# MKE1xFxxxVLH.net
KiCad netlist of a schematic drawn in Altium Designer
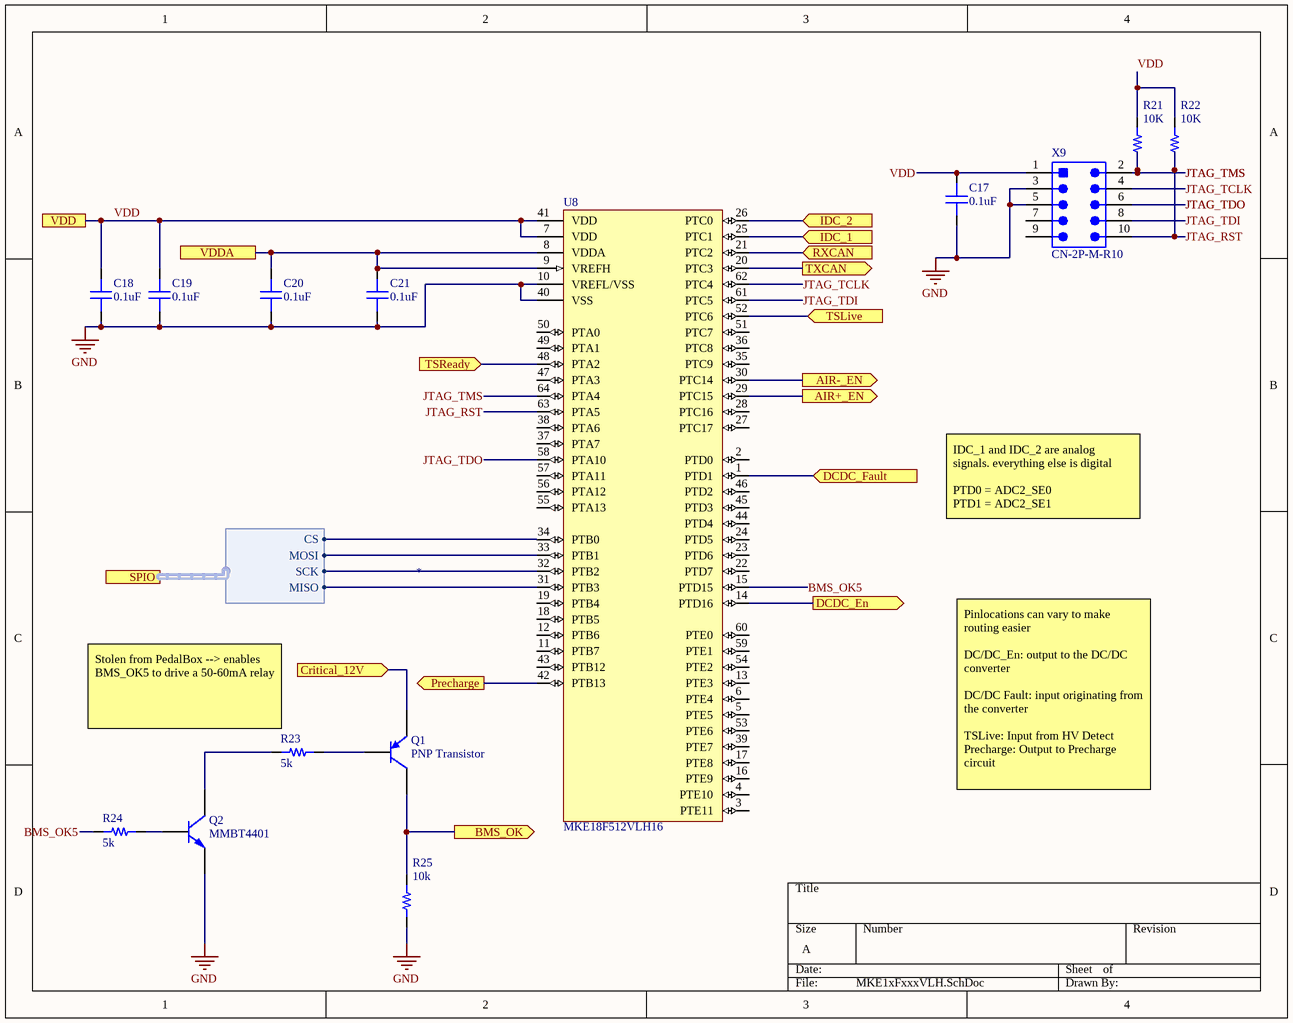
[diagram p0: MKE1xFxxxVLH.SchDoc]

(export (version "E")
  (design (tool "Eeschema 10.0.6"))
  (components
    (comp (ref "C17")
      (value "capacitor")
      (footprint "0603")
      (description "Generic 0603 capacitor")
      (fields (field (name "CAPACITANCE") "0.1uF") (field (name "VOLTAGE") "50"))
      (libsource (lib "altlib") (part "capacitor"))
    )
    (comp (ref "C18")
      (value "capacitor")
      (footprint "0603")
      (description "Generic 0603 capacitor")
      (fields (field (name "CAPACITANCE") "0.1uF") (field (name "VOLTAGE") "50"))
      (libsource (lib "altlib") (part "capacitor"))
    )
    (comp (ref "C19")
      (value "capacitor")
      (footprint "0603")
      (description "Generic 0603 capacitor")
      (fields (field (name "CAPACITANCE") "0.1uF") (field (name "VOLTAGE") "50"))
      (libsource (lib "altlib") (part "capacitor"))
    )
    (comp (ref "C20")
      (value "capacitor")
      (footprint "0603")
      (description "Generic 0603 capacitor")
      (fields (field (name "CAPACITANCE") "0.1uF") (field (name "VOLTAGE") "50"))
      (libsource (lib "altlib") (part "capacitor"))
    )
    (comp (ref "C21")
      (value "capacitor")
      (footprint "0603")
      (description "Generic 0603 capacitor")
      (fields (field (name "CAPACITANCE") "0.1uF") (field (name "VOLTAGE") "50"))
      (libsource (lib "altlib") (part "capacitor"))
    )
    (comp (ref "Q1")
      (value "PNP Transistor")
      (footprint "SOT23-3")
      (description "Bipolar (BJT) Transistor PNP 25V 1.5A 100MHz")
      (fields (field (name "POWER") "625") (field (name "CREATEDBY") "Kevin"))
      (libsource (lib "altlib") (part "PNP Transistor"))
    )
    (comp (ref "Q2") (value "MMBT4401") (footprint "SOT23-3") (libsource (lib "altlib") (part "MMBT4401")))
    (comp (ref "R21")
      (value "10K")
      (footprint "RES 0603/1608")
      (fields (field (name "RESISTANCE") "10K"))
      (libsource (lib "altlib") (part "Resistor"))
    )
    (comp (ref "R22")
      (value "10K")
      (footprint "RES 0603/1608")
      (fields (field (name "RESISTANCE") "10K"))
      (libsource (lib "altlib") (part "Resistor"))
    )
    (comp (ref "R23")
      (value "5k")
      (footprint "RES 0603/1608")
      (fields (field (name "RESISTANCE") "5k"))
      (libsource (lib "altlib") (part "Resistor"))
    )
    (comp (ref "R24")
      (value "5k")
      (footprint "RES 0603/1608")
      (fields (field (name "RESISTANCE") "5k"))
      (libsource (lib "altlib") (part "Resistor"))
    )
    (comp (ref "R25")
      (value "10k")
      (footprint "RES 0603/1608")
      (fields (field (name "RESISTANCE") "10k"))
      (libsource (lib "altlib") (part "Resistor"))
    )
    (comp (ref "U8")
      (value "MKE18F512VLH16")
      (footprint "TQFP64")
      (description "32b NXP Microcontroller")
      (libsource (lib "altlib") (part "MKE18F512VLH16"))
    )
    (comp (ref "X9")
      (value "CN-2P-M-R10")
      (footprint "HDR2X5_SMT")
      (description "CONN_TE_2X5POS")
      (libsource (lib "altlib") (part "CN-2P-M-R10"))
    )
  )
  (nets
    (net (code "2") (name "/AIR+_EN") (class "Default")
      (node (ref "U8") (pin "29") (pinfunction "PTC15_29") (pintype "bidirectional"))
    )
    (net (code "3") (name "/AIR-_EN") (class "Default")
      (node (ref "U8") (pin "30") (pinfunction "PTC14_30") (pintype "bidirectional"))
    )
    (net (code "4") (name "/BMS_OK") (class "Default")
      (node (ref "Q1") (pin "3") (pinfunction "C_3") (pintype "passive"))
      (node (ref "R25") (pin "2") (pinfunction "2_2") (pintype "passive"))
    )
    (net (code "5") (name "/BMS_OK5") (class "Default")
      (node (ref "R24") (pin "2") (pinfunction "2_2") (pintype "passive"))
      (node (ref "U8") (pin "15") (pinfunction "PTD15_15") (pintype "bidirectional"))
    )
    (net (code "6") (name "/CS") (class "Default")
      (node (ref "U8") (pin "34") (pinfunction "PTB0_34") (pintype "bidirectional"))
    )
    (net (code "7") (name "/Critical_12V") (class "Default")
      (node (ref "Q1") (pin "2") (pinfunction "E_2") (pintype "passive"))
    )
    (net (code "8") (name "/DCDC_En") (class "Default")
      (node (ref "U8") (pin "14") (pinfunction "PTD16_14") (pintype "bidirectional"))
    )
    (net (code "9") (name "/DCDC_Fault") (class "Default")
      (node (ref "U8") (pin "1") (pinfunction "PTD1_1") (pintype "bidirectional"))
    )
    (net (code "10") (name "/IDC_1") (class "Default")
      (node (ref "U8") (pin "25") (pinfunction "PTC1_25") (pintype "bidirectional"))
    )
    (net (code "11") (name "/IDC_2") (class "Default")
      (node (ref "U8") (pin "26") (pinfunction "PTC0_26") (pintype "bidirectional"))
    )
    (net (code "12") (name "/JTAG_RST") (class "Default")
      (node (ref "R22") (pin "1") (pinfunction "1_1") (pintype "passive"))
      (node (ref "U8") (pin "63") (pinfunction "PTA5_63") (pintype "bidirectional"))
      (node (ref "X9") (pin "10") (pinfunction "10_10") (pintype "passive"))
    )
    (net (code "13") (name "/JTAG_TCLK") (class "Default")
      (node (ref "U8") (pin "62") (pinfunction "PTC4_62") (pintype "bidirectional"))
      (node (ref "X9") (pin "4") (pinfunction "4_4") (pintype "passive"))
    )
    (net (code "14") (name "/JTAG_TDI") (class "Default")
      (node (ref "U8") (pin "61") (pinfunction "PTC5_61") (pintype "bidirectional"))
      (node (ref "X9") (pin "8") (pinfunction "8_8") (pintype "passive"))
    )
    (net (code "15") (name "/JTAG_TDO") (class "Default")
      (node (ref "U8") (pin "58") (pinfunction "PTA10_58") (pintype "bidirectional"))
      (node (ref "X9") (pin "6") (pinfunction "6_6") (pintype "passive"))
    )
    (net (code "16") (name "/JTAG_TMS") (class "Default")
      (node (ref "R21") (pin "1") (pinfunction "1_1") (pintype "passive"))
      (node (ref "U8") (pin "64") (pinfunction "PTA4_64") (pintype "bidirectional"))
      (node (ref "X9") (pin "2") (pinfunction "2_2") (pintype "passive"))
    )
    (net (code "17") (name "/MISO") (class "Default")
      (node (ref "U8") (pin "31") (pinfunction "PTB3_31") (pintype "bidirectional"))
    )
    (net (code "18") (name "/MOSI") (class "Default")
      (node (ref "U8") (pin "33") (pinfunction "PTB1_33") (pintype "bidirectional"))
    )
    (net (code "19") (name "/Precharge") (class "Default")
      (node (ref "U8") (pin "42") (pinfunction "PTB13_42") (pintype "bidirectional"))
    )
    (net (code "20") (name "/RXCAN") (class "Default")
      (node (ref "U8") (pin "21") (pinfunction "PTC2_21") (pintype "bidirectional"))
    )
    (net (code "21") (name "/SCK") (class "Default")
      (node (ref "U8") (pin "32") (pinfunction "PTB2_32") (pintype "bidirectional"))
    )
    (net (code "22") (name "/TSLive") (class "Default")
      (node (ref "U8") (pin "52") (pinfunction "PTC6_52") (pintype "bidirectional"))
    )
    (net (code "23") (name "/TSReady") (class "Default")
      (node (ref "U8") (pin "48") (pinfunction "PTA2_48") (pintype "bidirectional"))
    )
    (net (code "24") (name "/TXCAN") (class "Default")
      (node (ref "U8") (pin "20") (pinfunction "PTC3_20") (pintype "bidirectional"))
    )
    (net (code "25") (name "/VDD") (class "Default")
      (node (ref "C17") (pin "2") (pinfunction "2_2") (pintype "passive"))
      (node (ref "C18") (pin "2") (pinfunction "2_2") (pintype "passive"))
      (node (ref "C19") (pin "2") (pinfunction "2_2") (pintype "passive"))
      (node (ref "R21") (pin "2") (pinfunction "2_2") (pintype "passive"))
      (node (ref "R22") (pin "2") (pinfunction "2_2") (pintype "passive"))
      (node (ref "U8") (pin "41") (pinfunction "VDD_41") (pintype "passive"))
      (node (ref "U8") (pin "7") (pinfunction "VDD_7") (pintype "passive"))
      (node (ref "X9") (pin "1") (pinfunction "1_1") (pintype "passive"))
    )
    (net (code "26") (name "/VDDA") (class "Default")
      (node (ref "C20") (pin "2") (pinfunction "2_2") (pintype "passive"))
      (node (ref "C21") (pin "2") (pinfunction "2_2") (pintype "passive"))
      (node (ref "U8") (pin "8") (pinfunction "VDDA_8") (pintype "passive"))
      (node (ref "U8") (pin "9") (pinfunction "VREFH_9") (pintype "input"))
    )
    (net (code "28") (name "GND") (class "Default")
      (node (ref "C17") (pin "1") (pinfunction "1_1") (pintype "passive"))
      (node (ref "C18") (pin "1") (pinfunction "1_1") (pintype "passive"))
      (node (ref "C19") (pin "1") (pinfunction "1_1") (pintype "passive"))
      (node (ref "C20") (pin "1") (pinfunction "1_1") (pintype "passive"))
      (node (ref "C21") (pin "1") (pinfunction "1_1") (pintype "passive"))
      (node (ref "Q2") (pin "2") (pinfunction "E_2") (pintype "passive"))
      (node (ref "R25") (pin "1") (pinfunction "1_1") (pintype "passive"))
      (node (ref "U8") (pin "10") (pinfunction "VREFL/VSS_10") (pintype "passive"))
      (node (ref "U8") (pin "40") (pinfunction "VSS_40") (pintype "passive"))
      (node (ref "X9") (pin "3") (pinfunction "3_3") (pintype "passive"))
      (node (ref "X9") (pin "5") (pinfunction "5_5") (pintype "passive"))
    )
    (net (code "29") (name "Net-(Q1-B)") (class "Default")
      (node (ref "Q1") (pin "1") (pinfunction "B_1") (pintype "passive"))
      (node (ref "R23") (pin "1") (pinfunction "1_1") (pintype "passive"))
    )
    (net (code "30") (name "Net-(Q2-B)") (class "Default")
      (node (ref "Q2") (pin "1") (pinfunction "B_1") (pintype "passive"))
      (node (ref "R24") (pin "1") (pinfunction "1_1") (pintype "passive"))
    )
    (net (code "31") (name "Net-(Q2-C)") (class "Default")
      (node (ref "Q2") (pin "3") (pinfunction "C_3") (pintype "passive"))
      (node (ref "R23") (pin "2") (pinfunction "2_2") (pintype "passive"))
    )
    (net (code "32") (name "unconnected-(U8-PTA0-Pad50)") (class "Default")
      (node (ref "U8") (pin "50") (pinfunction "PTA0_50") (pintype "bidirectional"))
    )
    (net (code "33") (name "unconnected-(U8-PTA1-Pad49)") (class "Default")
      (node (ref "U8") (pin "49") (pinfunction "PTA1_49") (pintype "bidirectional"))
    )
    (net (code "34") (name "unconnected-(U8-PTA3-Pad47)") (class "Default")
      (node (ref "U8") (pin "47") (pinfunction "PTA3_47") (pintype "bidirectional"))
    )
    (net (code "35") (name "unconnected-(U8-PTA6-Pad38)") (class "Default")
      (node (ref "U8") (pin "38") (pinfunction "PTA6_38") (pintype "bidirectional"))
    )
    (net (code "36") (name "unconnected-(U8-PTA7-Pad37)") (class "Default")
      (node (ref "U8") (pin "37") (pinfunction "PTA7_37") (pintype "bidirectional"))
    )
    (net (code "37") (name "unconnected-(U8-PTA11-Pad57)") (class "Default")
      (node (ref "U8") (pin "57") (pinfunction "PTA11_57") (pintype "bidirectional"))
    )
    (net (code "38") (name "unconnected-(U8-PTA12-Pad56)") (class "Default")
      (node (ref "U8") (pin "56") (pinfunction "PTA12_56") (pintype "bidirectional"))
    )
    (net (code "39") (name "unconnected-(U8-PTA13-Pad55)") (class "Default")
      (node (ref "U8") (pin "55") (pinfunction "PTA13_55") (pintype "bidirectional"))
    )
    (net (code "40") (name "unconnected-(U8-PTB4-Pad19)") (class "Default")
      (node (ref "U8") (pin "19") (pinfunction "PTB4_19") (pintype "bidirectional"))
    )
    (net (code "41") (name "unconnected-(U8-PTB5-Pad18)") (class "Default")
      (node (ref "U8") (pin "18") (pinfunction "PTB5_18") (pintype "bidirectional"))
    )
    (net (code "42") (name "unconnected-(U8-PTB6-Pad12)") (class "Default")
      (node (ref "U8") (pin "12") (pinfunction "PTB6_12") (pintype "bidirectional"))
    )
    (net (code "43") (name "unconnected-(U8-PTB7-Pad11)") (class "Default")
      (node (ref "U8") (pin "11") (pinfunction "PTB7_11") (pintype "bidirectional"))
    )
    (net (code "44") (name "unconnected-(U8-PTB12-Pad43)") (class "Default")
      (node (ref "U8") (pin "43") (pinfunction "PTB12_43") (pintype "bidirectional"))
    )
    (net (code "45") (name "unconnected-(U8-PTC7-Pad51)") (class "Default")
      (node (ref "U8") (pin "51") (pinfunction "PTC7_51") (pintype "bidirectional"))
    )
    (net (code "46") (name "unconnected-(U8-PTC8-Pad36)") (class "Default")
      (node (ref "U8") (pin "36") (pinfunction "PTC8_36") (pintype "bidirectional"))
    )
    (net (code "47") (name "unconnected-(U8-PTC9-Pad35)") (class "Default")
      (node (ref "U8") (pin "35") (pinfunction "PTC9_35") (pintype "bidirectional"))
    )
    (net (code "48") (name "unconnected-(U8-PTC16-Pad28)") (class "Default")
      (node (ref "U8") (pin "28") (pinfunction "PTC16_28") (pintype "bidirectional"))
    )
    (net (code "49") (name "unconnected-(U8-PTC17-Pad27)") (class "Default")
      (node (ref "U8") (pin "27") (pinfunction "PTC17_27") (pintype "bidirectional"))
    )
    (net (code "50") (name "unconnected-(U8-PTD0-Pad2)") (class "Default")
      (node (ref "U8") (pin "2") (pinfunction "PTD0_2") (pintype "bidirectional"))
    )
    (net (code "51") (name "unconnected-(U8-PTD2-Pad46)") (class "Default")
      (node (ref "U8") (pin "46") (pinfunction "PTD2_46") (pintype "bidirectional"))
    )
    (net (code "52") (name "unconnected-(U8-PTD3-Pad45)") (class "Default")
      (node (ref "U8") (pin "45") (pinfunction "PTD3_45") (pintype "bidirectional"))
    )
    (net (code "53") (name "unconnected-(U8-PTD4-Pad44)") (class "Default")
      (node (ref "U8") (pin "44") (pinfunction "PTD4_44") (pintype "bidirectional"))
    )
    (net (code "54") (name "unconnected-(U8-PTD5-Pad24)") (class "Default")
      (node (ref "U8") (pin "24") (pinfunction "PTD5_24") (pintype "bidirectional"))
    )
    (net (code "55") (name "unconnected-(U8-PTD6-Pad23)") (class "Default")
      (node (ref "U8") (pin "23") (pinfunction "PTD6_23") (pintype "bidirectional"))
    )
    (net (code "56") (name "unconnected-(U8-PTD7-Pad22)") (class "Default")
      (node (ref "U8") (pin "22") (pinfunction "PTD7_22") (pintype "bidirectional"))
    )
    (net (code "57") (name "unconnected-(U8-PTE0-Pad60)") (class "Default")
      (node (ref "U8") (pin "60") (pinfunction "PTE0_60") (pintype "bidirectional"))
    )
    (net (code "58") (name "unconnected-(U8-PTE1-Pad59)") (class "Default")
      (node (ref "U8") (pin "59") (pinfunction "PTE1_59") (pintype "bidirectional"))
    )
    (net (code "59") (name "unconnected-(U8-PTE2-Pad54)") (class "Default")
      (node (ref "U8") (pin "54") (pinfunction "PTE2_54") (pintype "bidirectional"))
    )
    (net (code "60") (name "unconnected-(U8-PTE3-Pad13)") (class "Default")
      (node (ref "U8") (pin "13") (pinfunction "PTE3_13") (pintype "bidirectional"))
    )
    (net (code "61") (name "unconnected-(U8-PTE4-Pad6)") (class "Default")
      (node (ref "U8") (pin "6") (pinfunction "PTE4_6") (pintype "bidirectional"))
    )
    (net (code "62") (name "unconnected-(U8-PTE5-Pad5)") (class "Default")
      (node (ref "U8") (pin "5") (pinfunction "PTE5_5") (pintype "bidirectional"))
    )
    (net (code "63") (name "unconnected-(U8-PTE6-Pad53)") (class "Default")
      (node (ref "U8") (pin "53") (pinfunction "PTE6_53") (pintype "bidirectional"))
    )
    (net (code "64") (name "unconnected-(U8-PTE7-Pad39)") (class "Default")
      (node (ref "U8") (pin "39") (pinfunction "PTE7_39") (pintype "bidirectional"))
    )
    (net (code "65") (name "unconnected-(U8-PTE8-Pad17)") (class "Default")
      (node (ref "U8") (pin "17") (pinfunction "PTE8_17") (pintype "bidirectional"))
    )
    (net (code "66") (name "unconnected-(U8-PTE9-Pad16)") (class "Default")
      (node (ref "U8") (pin "16") (pinfunction "PTE9_16") (pintype "bidirectional"))
    )
    (net (code "67") (name "unconnected-(U8-PTE10-Pad4)") (class "Default")
      (node (ref "U8") (pin "4") (pinfunction "PTE10_4") (pintype "bidirectional"))
    )
    (net (code "68") (name "unconnected-(U8-PTE11-Pad3)") (class "Default")
      (node (ref "U8") (pin "3") (pinfunction "PTE11_3") (pintype "bidirectional"))
    )
    (net (code "69") (name "unconnected-(X9-Pad7)") (class "Default")
      (node (ref "X9") (pin "7") (pinfunction "7_7") (pintype "passive"))
    )
    (net (code "70") (name "unconnected-(X9-Pad9)") (class "Default")
      (node (ref "X9") (pin "9") (pinfunction "9_9") (pintype "passive"))
    )
  )
)
